# GPduino-T.net
KiCad netlist of a schematic drawn in EAGLE
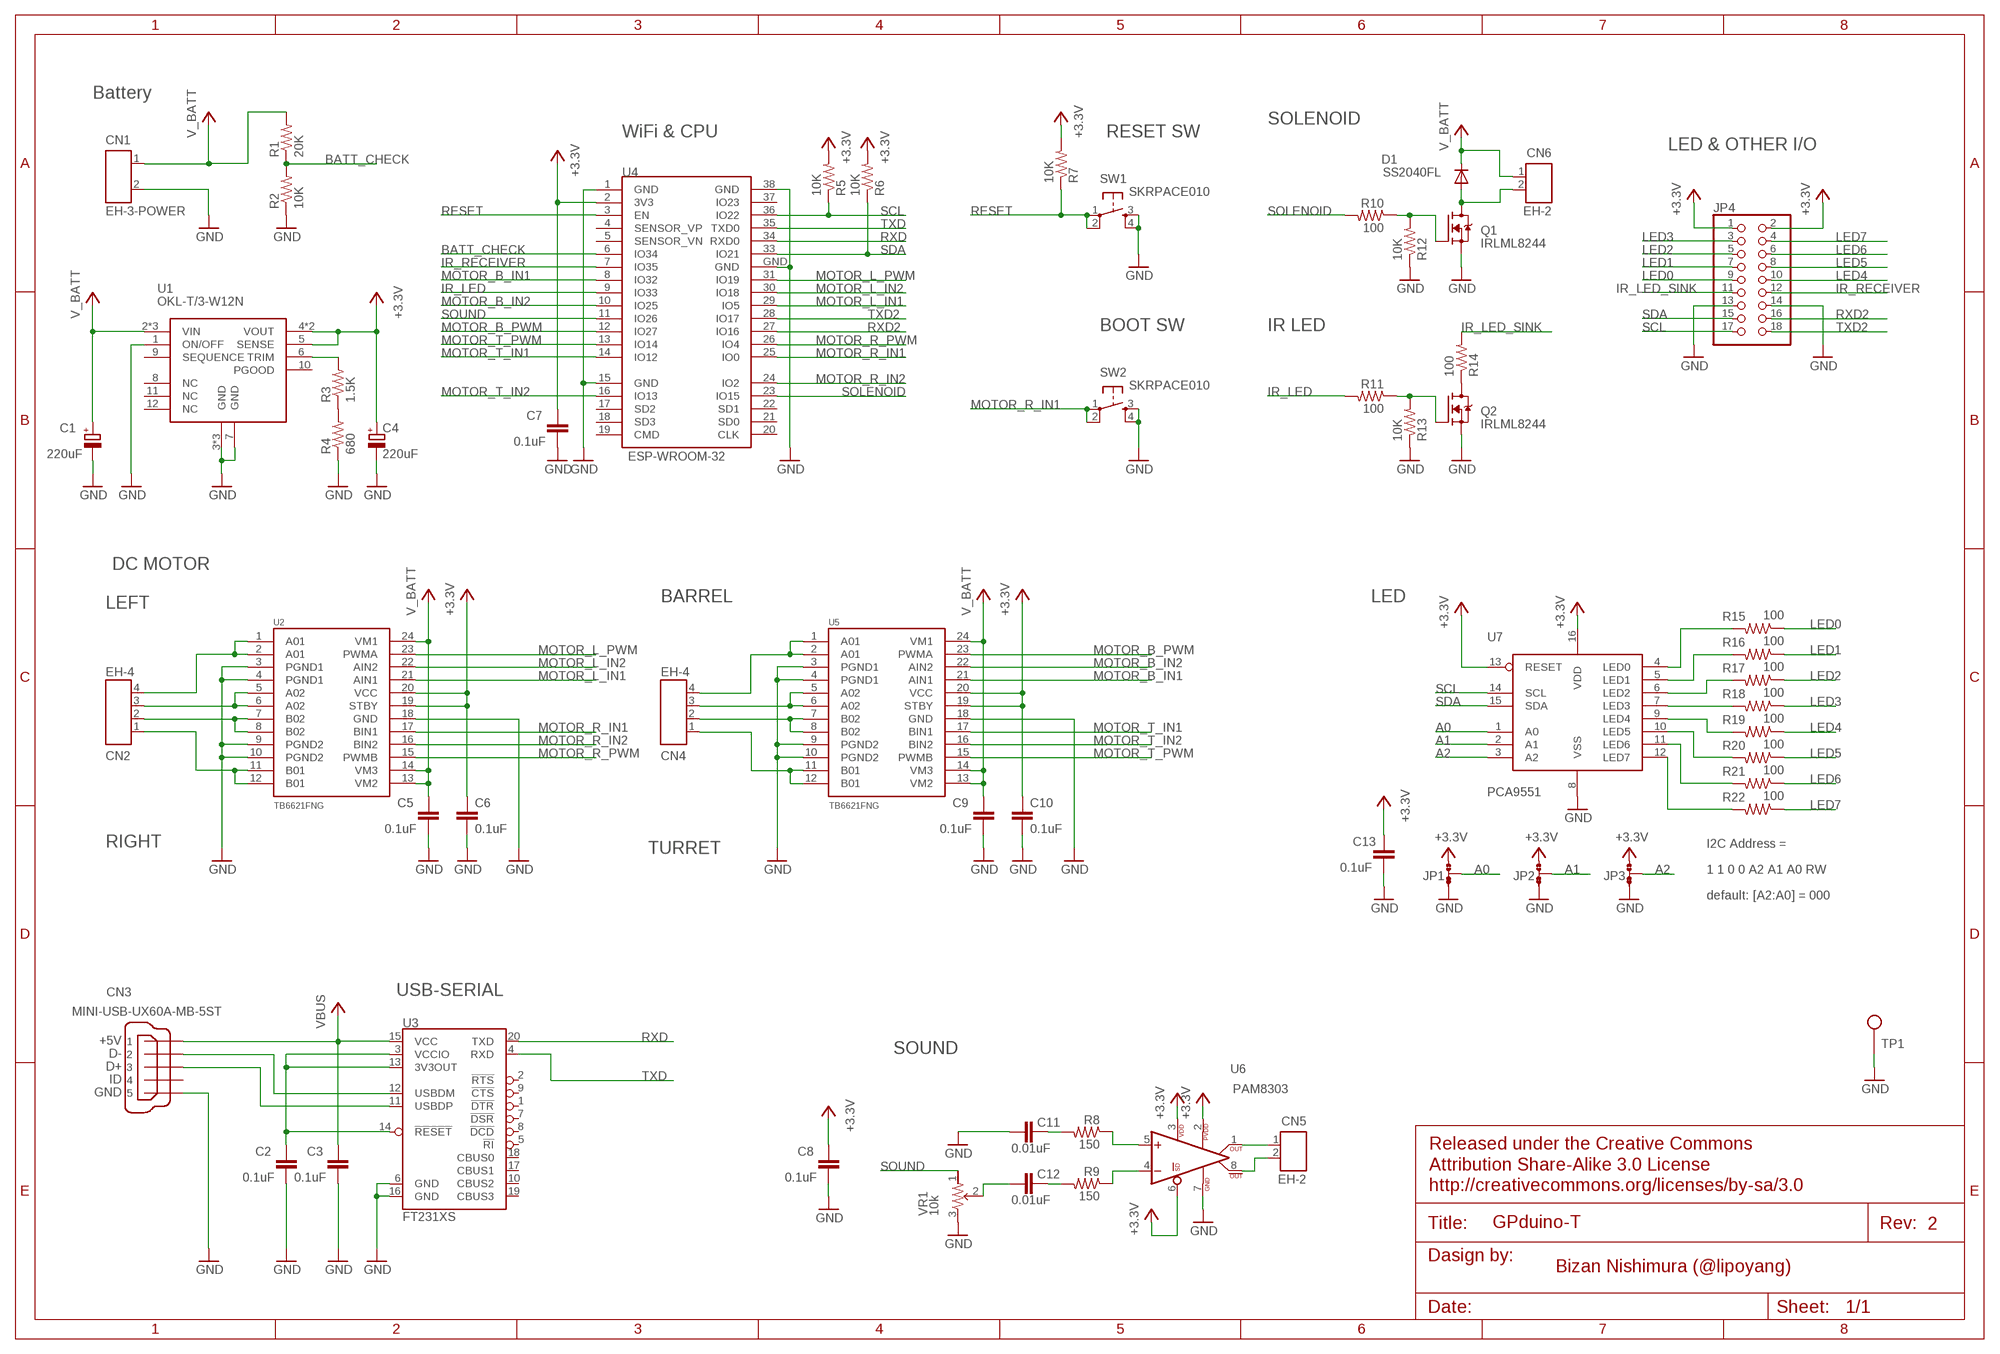
[diagram p0: schematic, sheet 1]

(export (version "E")
  (design (tool "Eeschema 10.0.6"))
  (components
    (comp (ref "C1")
      (value "220uF")
      (footprint "eagle-import:UD-6,3X7,7_NICHICON")
      (libsource (lib "eagle-import") (part "CPOL-EUUD-6,3X7,7"))
    )
    (comp (ref "C2")
      (value "0.1uF")
      (footprint "eagle-import:C1608")
      (libsource (lib "eagle-import") (part "C-EUC1608"))
    )
    (comp (ref "C3")
      (value "0.1uF")
      (footprint "eagle-import:C1608")
      (libsource (lib "eagle-import") (part "C-EUC1608"))
    )
    (comp (ref "C4")
      (value "220uF")
      (footprint "eagle-import:UD-6,3X7,7_NICHICON")
      (libsource (lib "eagle-import") (part "CPOL-EUUD-6,3X7,7"))
    )
    (comp (ref "C5")
      (value "0.1uF")
      (footprint "eagle-import:C1608")
      (libsource (lib "eagle-import") (part "C-EUC1608"))
    )
    (comp (ref "C6")
      (value "0.1uF")
      (footprint "eagle-import:C1608")
      (libsource (lib "eagle-import") (part "C-EUC1608"))
    )
    (comp (ref "C7")
      (value "0.1uF")
      (footprint "eagle-import:C1608")
      (libsource (lib "eagle-import") (part "C-EUC1608"))
    )
    (comp (ref "C8")
      (value "0.1uF")
      (footprint "eagle-import:C1608")
      (libsource (lib "eagle-import") (part "C-EUC1608"))
    )
    (comp (ref "C9")
      (value "0.1uF")
      (footprint "eagle-import:C1608")
      (libsource (lib "eagle-import") (part "C-EUC1608"))
    )
    (comp (ref "C10")
      (value "0.1uF")
      (footprint "eagle-import:C1608")
      (libsource (lib "eagle-import") (part "C-EUC1608"))
    )
    (comp (ref "C11")
      (value "0.01uF")
      (footprint "eagle-import:C1608")
      (libsource (lib "eagle-import") (part "C-EUC1608"))
    )
    (comp (ref "C12")
      (value "0.01uF")
      (footprint "eagle-import:C1608")
      (libsource (lib "eagle-import") (part "C-EUC1608"))
    )
    (comp (ref "C13")
      (value "0.1uF")
      (footprint "eagle-import:C1608")
      (libsource (lib "eagle-import") (part "C-EUC1608"))
    )
    (comp (ref "CN1")
      (value "EH-3-POWER")
      (footprint "eagle-import:EH-3-POWER")
      (libsource (lib "eagle-import") (part "EH-3-POWER"))
    )
    (comp (ref "CN2")
      (value "EH-4")
      (footprint "eagle-import:EH-4")
      (libsource (lib "eagle-import") (part "EH-4"))
    )
    (comp (ref "CN3")
      (value "MINI-USB-UX60A-MB-5ST")
      (footprint "eagle-import:UX60A-MB-5ST")
      (libsource (lib "eagle-import") (part "MINI-USB-UX60A-MB-5ST"))
    )
    (comp (ref "CN4")
      (value "EH-4")
      (footprint "eagle-import:EH-4")
      (libsource (lib "eagle-import") (part "EH-4"))
    )
    (comp (ref "CN5")
      (value "EH-2")
      (footprint "eagle-import:EH-2")
      (libsource (lib "eagle-import") (part "EH-2"))
    )
    (comp (ref "CN6")
      (value "EH-2")
      (footprint "eagle-import:EH-2")
      (libsource (lib "eagle-import") (part "EH-2"))
    )
    (comp (ref "D1")
      (value "SS2040FL")
      (footprint "eagle-import:SOD123")
      (libsource (lib "eagle-import") (part "DIODE-SOD123"))
    )
    (comp (ref "JP1")
      (value "JUMP-SHORTB")
      (footprint "eagle-import:JUMP-SHORT")
      (libsource (lib "eagle-import") (part "JUMP-SHORTB"))
    )
    (comp (ref "JP2")
      (value "JUMP-SHORTB")
      (footprint "eagle-import:JUMP-SHORT")
      (libsource (lib "eagle-import") (part "JUMP-SHORTB"))
    )
    (comp (ref "JP3")
      (value "JUMP-SHORTB")
      (footprint "eagle-import:JUMP-SHORT")
      (libsource (lib "eagle-import") (part "JUMP-SHORTB"))
    )
    (comp (ref "JP4")
      (value "PINHD-2X9")
      (footprint "eagle-import:2X09")
      (libsource (lib "eagle-import") (part "PINHD-2X9"))
    )
    (comp (ref "Q1")
      (value "IRLML8244")
      (footprint "eagle-import:SOT23")
      (libsource (lib "eagle-import") (part "IRLML8244"))
    )
    (comp (ref "Q2")
      (value "IRLML8244")
      (footprint "eagle-import:SOT23")
      (libsource (lib "eagle-import") (part "IRLML8244"))
    )
    (comp (ref "R1")
      (value "20K")
      (footprint "eagle-import:0603-RES")
      (libsource (lib "eagle-import") (part "RESISTOR0603-RES"))
    )
    (comp (ref "R2")
      (value "10K")
      (footprint "eagle-import:0603-RES")
      (libsource (lib "eagle-import") (part "RESISTOR0603-RES"))
    )
    (comp (ref "R3")
      (value "1.5K")
      (footprint "eagle-import:0603-RES")
      (libsource (lib "eagle-import") (part "RESISTOR0603-RES"))
    )
    (comp (ref "R4")
      (value "680")
      (footprint "eagle-import:0603-RES")
      (libsource (lib "eagle-import") (part "RESISTOR0603-RES"))
    )
    (comp (ref "R5")
      (value "10K")
      (footprint "eagle-import:0603-RES")
      (libsource (lib "eagle-import") (part "RESISTOR0603-RES"))
    )
    (comp (ref "R6")
      (value "10K")
      (footprint "eagle-import:0603-RES")
      (libsource (lib "eagle-import") (part "RESISTOR0603-RES"))
    )
    (comp (ref "R7")
      (value "10K")
      (footprint "eagle-import:0603-RES")
      (libsource (lib "eagle-import") (part "RESISTOR0603-RES"))
    )
    (comp (ref "R8")
      (value "150")
      (footprint "eagle-import:0603-RES")
      (libsource (lib "eagle-import") (part "RESISTOR0603-RES"))
    )
    (comp (ref "R9")
      (value "150")
      (footprint "eagle-import:0603-RES")
      (libsource (lib "eagle-import") (part "RESISTOR0603-RES"))
    )
    (comp (ref "R10")
      (value "100")
      (footprint "eagle-import:0603-RES")
      (libsource (lib "eagle-import") (part "RESISTOR0603-RES"))
    )
    (comp (ref "R11")
      (value "100")
      (footprint "eagle-import:0603-RES")
      (libsource (lib "eagle-import") (part "RESISTOR0603-RES"))
    )
    (comp (ref "R12")
      (value "10K")
      (footprint "eagle-import:0603-RES")
      (libsource (lib "eagle-import") (part "RESISTOR0603-RES"))
    )
    (comp (ref "R13")
      (value "10K")
      (footprint "eagle-import:0603-RES")
      (libsource (lib "eagle-import") (part "RESISTOR0603-RES"))
    )
    (comp (ref "R14")
      (value "100")
      (footprint "eagle-import:0603-RES")
      (libsource (lib "eagle-import") (part "RESISTOR0603-RES"))
    )
    (comp (ref "R15")
      (value "100")
      (footprint "eagle-import:0603-RES")
      (libsource (lib "eagle-import") (part "RESISTOR0603-RES"))
    )
    (comp (ref "R16")
      (value "100")
      (footprint "eagle-import:0603-RES")
      (libsource (lib "eagle-import") (part "RESISTOR0603-RES"))
    )
    (comp (ref "R17")
      (value "100")
      (footprint "eagle-import:0603-RES")
      (libsource (lib "eagle-import") (part "RESISTOR0603-RES"))
    )
    (comp (ref "R18")
      (value "100")
      (footprint "eagle-import:0603-RES")
      (libsource (lib "eagle-import") (part "RESISTOR0603-RES"))
    )
    (comp (ref "R19")
      (value "100")
      (footprint "eagle-import:0603-RES")
      (libsource (lib "eagle-import") (part "RESISTOR0603-RES"))
    )
    (comp (ref "R20")
      (value "100")
      (footprint "eagle-import:0603-RES")
      (libsource (lib "eagle-import") (part "RESISTOR0603-RES"))
    )
    (comp (ref "R21")
      (value "100")
      (footprint "eagle-import:0603-RES")
      (libsource (lib "eagle-import") (part "RESISTOR0603-RES"))
    )
    (comp (ref "R22")
      (value "100")
      (footprint "eagle-import:0603-RES")
      (libsource (lib "eagle-import") (part "RESISTOR0603-RES"))
    )
    (comp (ref "SW1")
      (value "SKRPACE010")
      (footprint "eagle-import:SKRPACE010")
      (libsource (lib "eagle-import") (part "SKRPACE010"))
    )
    (comp (ref "SW2")
      (value "SKRPACE010")
      (footprint "eagle-import:SKRPACE010")
      (libsource (lib "eagle-import") (part "SKRPACE010"))
    )
    (comp (ref "TP1")
      (value "TEST_PIN")
      (footprint "eagle-import:TEST_PIN")
      (libsource (lib "eagle-import") (part "TEST_PIN"))
    )
    (comp (ref "U1")
      (value "OKL-T/3-W12N")
      (footprint "eagle-import:OKL-T_X-WXXN")
      (libsource (lib "eagle-import") (part "OKL-T/6-W12N"))
    )
    (comp (ref "U2")
      (value "TB6621FNG")
      (footprint "eagle-import:SSOP24")
      (libsource (lib "eagle-import") (part "TB6621FNG"))
    )
    (comp (ref "U3")
      (value "FT231XS")
      (footprint "eagle-import:SSOP20")
      (libsource (lib "eagle-import") (part "FT231XS"))
    )
    (comp (ref "U4")
      (value "ESP-WROOM-32")
      (footprint "eagle-import:ESP-WROOM-32")
      (libsource (lib "eagle-import") (part "ESP-WROOM-32"))
    )
    (comp (ref "U5")
      (value "TB6621FNG")
      (footprint "eagle-import:SSOP24")
      (libsource (lib "eagle-import") (part "TB6621FNG"))
    )
    (comp (ref "U6")
      (value "PAM8303")
      (footprint "eagle-import:MSOP8")
      (libsource (lib "eagle-import") (part "PAM8303"))
    )
    (comp (ref "U7")
      (value "PCA9551")
      (footprint "eagle-import:TSSOP16")
      (libsource (lib "eagle-import") (part "PCA9551"))
    )
    (comp (ref "VR1")
      (value "10k")
      (footprint "eagle-import:EVM3Y")
      (libsource (lib "eagle-import") (part "R-TRIMM"))
    )
  )
  (nets
    (net (code "1") (name "+3.3V") (class "Default")
      (node (ref "C10") (pin "1") (pinfunction "1_1") (pintype "passive"))
      (node (ref "C13") (pin "1") (pinfunction "1_1") (pintype "passive"))
      (node (ref "C4") (pin "+") (pinfunction "+_+") (pintype "passive"))
      (node (ref "C6") (pin "1") (pinfunction "1_1") (pintype "passive"))
      (node (ref "C7") (pin "1") (pinfunction "1_1") (pintype "passive"))
      (node (ref "C8") (pin "1") (pinfunction "1_1") (pintype "passive"))
      (node (ref "JP1") (pin "1") (pinfunction "1_1") (pintype "passive"))
      (node (ref "JP2") (pin "1") (pinfunction "1_1") (pintype "passive"))
      (node (ref "JP3") (pin "1") (pinfunction "1_1") (pintype "passive"))
      (node (ref "JP4") (pin "1") (pinfunction "1_1") (pintype "passive"))
      (node (ref "JP4") (pin "2") (pinfunction "2_2") (pintype "passive"))
      (node (ref "R5") (pin "2") (pinfunction "2_2") (pintype "passive"))
      (node (ref "R6") (pin "2") (pinfunction "2_2") (pintype "passive"))
      (node (ref "R7") (pin "2") (pinfunction "2_2") (pintype "passive"))
      (node (ref "U1") (pin "4") (pinfunction "VOUT_4") (pintype "power_in"))
      (node (ref "U1") (pin "4@1") (pinfunction "VOUT_4@1") (pintype "power_in"))
      (node (ref "U1") (pin "5") (pinfunction "SENSE_5") (pintype "input"))
      (node (ref "U2") (pin "19") (pinfunction "STBY_19") (pintype "bidirectional"))
      (node (ref "U2") (pin "20") (pinfunction "VCC_20") (pintype "bidirectional"))
      (node (ref "U4") (pin "2") (pinfunction "3V3_2") (pintype "power_in"))
      (node (ref "U5") (pin "19") (pinfunction "STBY_19") (pintype "bidirectional"))
      (node (ref "U5") (pin "20") (pinfunction "VCC_20") (pintype "bidirectional"))
      (node (ref "U6") (pin "2") (pinfunction "PVDD_2") (pintype "power_in"))
      (node (ref "U6") (pin "3") (pinfunction "VDD_3") (pintype "power_in"))
      (node (ref "U6") (pin "6") (pinfunction "SD_6") (pintype "input"))
      (node (ref "U7") (pin "13") (pinfunction "RESET_13") (pintype "input"))
      (node (ref "U7") (pin "16") (pinfunction "VDD_16") (pintype "power_in"))
    )
    (net (code "2") (name "/A0") (class "Default")
      (node (ref "JP1") (pin "2") (pinfunction "2_2") (pintype "passive"))
      (node (ref "U7") (pin "1") (pinfunction "A0_1") (pintype "input"))
    )
    (net (code "3") (name "/A1") (class "Default")
      (node (ref "JP2") (pin "2") (pinfunction "2_2") (pintype "passive"))
      (node (ref "U7") (pin "2") (pinfunction "A1_2") (pintype "input"))
    )
    (net (code "4") (name "/A2") (class "Default")
      (node (ref "JP3") (pin "2") (pinfunction "2_2") (pintype "passive"))
      (node (ref "U7") (pin "3") (pinfunction "A2_3") (pintype "input"))
    )
    (net (code "5") (name "/BATT_CHECK") (class "Default")
      (node (ref "R1") (pin "1") (pinfunction "1_1") (pintype "passive"))
      (node (ref "R2") (pin "2") (pinfunction "2_2") (pintype "passive"))
      (node (ref "U4") (pin "6") (pinfunction "IO34_6") (pintype "bidirectional"))
    )
    (net (code "6") (name "/IR_LED") (class "Default")
      (node (ref "R11") (pin "2") (pinfunction "2_2") (pintype "passive"))
      (node (ref "U4") (pin "9") (pinfunction "IO33_9") (pintype "bidirectional"))
    )
    (net (code "7") (name "/IR_LED_SINK") (class "Default")
      (node (ref "JP4") (pin "11") (pinfunction "11_11") (pintype "passive"))
      (node (ref "R14") (pin "2") (pinfunction "2_2") (pintype "passive"))
    )
    (net (code "8") (name "/IR_RECEIVER") (class "Default")
      (node (ref "JP4") (pin "12") (pinfunction "12_12") (pintype "passive"))
      (node (ref "U4") (pin "7") (pinfunction "IO35_7") (pintype "bidirectional"))
    )
    (net (code "9") (name "/LED0") (class "Default")
      (node (ref "JP4") (pin "9") (pinfunction "9_9") (pintype "passive"))
      (node (ref "R15") (pin "1") (pinfunction "1_1") (pintype "passive"))
    )
    (net (code "10") (name "/LED1") (class "Default")
      (node (ref "JP4") (pin "7") (pinfunction "7_7") (pintype "passive"))
      (node (ref "R16") (pin "1") (pinfunction "1_1") (pintype "passive"))
    )
    (net (code "11") (name "/LED2") (class "Default")
      (node (ref "JP4") (pin "5") (pinfunction "5_5") (pintype "passive"))
      (node (ref "R17") (pin "1") (pinfunction "1_1") (pintype "passive"))
    )
    (net (code "12") (name "/LED3") (class "Default")
      (node (ref "JP4") (pin "3") (pinfunction "3_3") (pintype "passive"))
      (node (ref "R18") (pin "1") (pinfunction "1_1") (pintype "passive"))
    )
    (net (code "13") (name "/LED4") (class "Default")
      (node (ref "JP4") (pin "10") (pinfunction "10_10") (pintype "passive"))
      (node (ref "R19") (pin "1") (pinfunction "1_1") (pintype "passive"))
    )
    (net (code "14") (name "/LED5") (class "Default")
      (node (ref "JP4") (pin "8") (pinfunction "8_8") (pintype "passive"))
      (node (ref "R20") (pin "1") (pinfunction "1_1") (pintype "passive"))
    )
    (net (code "15") (name "/LED6") (class "Default")
      (node (ref "JP4") (pin "6") (pinfunction "6_6") (pintype "passive"))
      (node (ref "R21") (pin "1") (pinfunction "1_1") (pintype "passive"))
    )
    (net (code "16") (name "/LED7") (class "Default")
      (node (ref "JP4") (pin "4") (pinfunction "4_4") (pintype "passive"))
      (node (ref "R22") (pin "1") (pinfunction "1_1") (pintype "passive"))
    )
    (net (code "17") (name "/MOTOR_B_IN1") (class "Default")
      (node (ref "U4") (pin "8") (pinfunction "IO32_8") (pintype "bidirectional"))
      (node (ref "U5") (pin "21") (pinfunction "AIN1_21") (pintype "bidirectional"))
    )
    (net (code "18") (name "/MOTOR_B_IN2") (class "Default")
      (node (ref "U4") (pin "10") (pinfunction "IO25_10") (pintype "bidirectional"))
      (node (ref "U5") (pin "22") (pinfunction "AIN2_22") (pintype "bidirectional"))
    )
    (net (code "19") (name "/MOTOR_B_PWM") (class "Default")
      (node (ref "U4") (pin "12") (pinfunction "IO27_12") (pintype "bidirectional"))
      (node (ref "U5") (pin "23") (pinfunction "PWMA_23") (pintype "bidirectional"))
    )
    (net (code "20") (name "/MOTOR_L_IN1") (class "Default")
      (node (ref "U2") (pin "21") (pinfunction "AIN1_21") (pintype "bidirectional"))
      (node (ref "U4") (pin "29") (pinfunction "IO5_29") (pintype "bidirectional"))
    )
    (net (code "21") (name "/MOTOR_L_IN2") (class "Default")
      (node (ref "U2") (pin "22") (pinfunction "AIN2_22") (pintype "bidirectional"))
      (node (ref "U4") (pin "30") (pinfunction "IO18_30") (pintype "bidirectional"))
    )
    (net (code "22") (name "/MOTOR_L_PWM") (class "Default")
      (node (ref "U2") (pin "23") (pinfunction "PWMA_23") (pintype "bidirectional"))
      (node (ref "U4") (pin "31") (pinfunction "IO19_31") (pintype "bidirectional"))
    )
    (net (code "23") (name "/MOTOR_R_IN1") (class "Default")
      (node (ref "SW2") (pin "1") (pinfunction "1_1") (pintype "passive"))
      (node (ref "SW2") (pin "2") (pinfunction "2_2") (pintype "passive"))
      (node (ref "U2") (pin "17") (pinfunction "BIN1_17") (pintype "bidirectional"))
      (node (ref "U4") (pin "25") (pinfunction "IO0_25") (pintype "bidirectional"))
    )
    (net (code "24") (name "/MOTOR_R_IN2") (class "Default")
      (node (ref "U2") (pin "16") (pinfunction "BIN2_16") (pintype "bidirectional"))
      (node (ref "U4") (pin "24") (pinfunction "IO2_24") (pintype "bidirectional"))
    )
    (net (code "25") (name "/MOTOR_R_PWM") (class "Default")
      (node (ref "U2") (pin "15") (pinfunction "PWMB_15") (pintype "bidirectional"))
      (node (ref "U4") (pin "26") (pinfunction "IO4_26") (pintype "bidirectional"))
    )
    (net (code "26") (name "/MOTOR_T_IN1") (class "Default")
      (node (ref "U4") (pin "14") (pinfunction "IO12_14") (pintype "bidirectional"))
      (node (ref "U5") (pin "17") (pinfunction "BIN1_17") (pintype "bidirectional"))
    )
    (net (code "27") (name "/MOTOR_T_IN2") (class "Default")
      (node (ref "U4") (pin "16") (pinfunction "IO13_16") (pintype "bidirectional"))
      (node (ref "U5") (pin "16") (pinfunction "BIN2_16") (pintype "bidirectional"))
    )
    (net (code "28") (name "/MOTOR_T_PWM") (class "Default")
      (node (ref "U4") (pin "13") (pinfunction "IO14_13") (pintype "bidirectional"))
      (node (ref "U5") (pin "15") (pinfunction "PWMB_15") (pintype "bidirectional"))
    )
    (net (code "29") (name "/RESET") (class "Default")
      (node (ref "R7") (pin "1") (pinfunction "1_1") (pintype "passive"))
      (node (ref "SW1") (pin "1") (pinfunction "1_1") (pintype "passive"))
      (node (ref "SW1") (pin "2") (pinfunction "2_2") (pintype "passive"))
      (node (ref "U4") (pin "3") (pinfunction "EN_3") (pintype "input"))
    )
    (net (code "30") (name "/RXD") (class "Default")
      (node (ref "U3") (pin "20") (pinfunction "TXD_20") (pintype "bidirectional"))
      (node (ref "U4") (pin "34") (pinfunction "RXD0_34") (pintype "bidirectional"))
    )
    (net (code "31") (name "/RXD2") (class "Default")
      (node (ref "JP4") (pin "16") (pinfunction "16_16") (pintype "passive"))
      (node (ref "U4") (pin "27") (pinfunction "IO16_27") (pintype "bidirectional"))
    )
    (net (code "32") (name "/SCL") (class "Default")
      (node (ref "JP4") (pin "17") (pinfunction "17_17") (pintype "passive"))
      (node (ref "R5") (pin "1") (pinfunction "1_1") (pintype "passive"))
      (node (ref "U4") (pin "36") (pinfunction "IO22_36") (pintype "bidirectional"))
      (node (ref "U7") (pin "14") (pinfunction "SCL_14") (pintype "bidirectional"))
    )
    (net (code "33") (name "/SDA") (class "Default")
      (node (ref "JP4") (pin "15") (pinfunction "15_15") (pintype "passive"))
      (node (ref "R6") (pin "1") (pinfunction "1_1") (pintype "passive"))
      (node (ref "U4") (pin "33") (pinfunction "IO21_33") (pintype "bidirectional"))
      (node (ref "U7") (pin "15") (pinfunction "SDA_15") (pintype "bidirectional"))
    )
    (net (code "34") (name "/SOLENOID") (class "Default")
      (node (ref "R10") (pin "2") (pinfunction "2_2") (pintype "passive"))
      (node (ref "U4") (pin "23") (pinfunction "IO15_23") (pintype "bidirectional"))
    )
    (net (code "35") (name "/SOUND") (class "Default")
      (node (ref "U4") (pin "11") (pinfunction "IO26_11") (pintype "bidirectional"))
      (node (ref "VR1") (pin "1") (pinfunction "E_1") (pintype "passive"))
    )
    (net (code "36") (name "/TXD") (class "Default")
      (node (ref "U3") (pin "4") (pinfunction "RXD_4") (pintype "bidirectional"))
      (node (ref "U4") (pin "35") (pinfunction "TXD0_35") (pintype "bidirectional"))
    )
    (net (code "37") (name "/TXD2") (class "Default")
      (node (ref "JP4") (pin "18") (pinfunction "18_18") (pintype "passive"))
      (node (ref "U4") (pin "28") (pinfunction "IO17_28") (pintype "bidirectional"))
    )
    (net (code "38") (name "GND") (class "Default")
      (node (ref "C1") (pin "-") (pinfunction "-_-") (pintype "passive"))
      (node (ref "C10") (pin "2") (pinfunction "2_2") (pintype "passive"))
      (node (ref "C11") (pin "2") (pinfunction "2_2") (pintype "passive"))
      (node (ref "C13") (pin "2") (pinfunction "2_2") (pintype "passive"))
      (node (ref "C2") (pin "2") (pinfunction "2_2") (pintype "passive"))
      (node (ref "C3") (pin "2") (pinfunction "2_2") (pintype "passive"))
      (node (ref "C4") (pin "-") (pinfunction "-_-") (pintype "passive"))
      (node (ref "C5") (pin "2") (pinfunction "2_2") (pintype "passive"))
      (node (ref "C6") (pin "2") (pinfunction "2_2") (pintype "passive"))
      (node (ref "C7") (pin "2") (pinfunction "2_2") (pintype "passive"))
      (node (ref "C8") (pin "2") (pinfunction "2_2") (pintype "passive"))
      (node (ref "C9") (pin "2") (pinfunction "2_2") (pintype "passive"))
      (node (ref "CN1") (pin "2") (pinfunction "2_2") (pintype "bidirectional"))
      (node (ref "CN3") (pin "5") (pinfunction "5_5") (pintype "input"))
      (node (ref "JP1") (pin "3") (pinfunction "3_3") (pintype "passive"))
      (node (ref "JP2") (pin "3") (pinfunction "3_3") (pintype "passive"))
      (node (ref "JP3") (pin "3") (pinfunction "3_3") (pintype "passive"))
      (node (ref "JP4") (pin "13") (pinfunction "13_13") (pintype "passive"))
      (node (ref "JP4") (pin "14") (pinfunction "14_14") (pintype "passive"))
      (node (ref "Q1") (pin "2") (pinfunction "S_2") (pintype "passive"))
      (node (ref "Q2") (pin "2") (pinfunction "S_2") (pintype "passive"))
      (node (ref "R12") (pin "1") (pinfunction "1_1") (pintype "passive"))
      (node (ref "R13") (pin "1") (pinfunction "1_1") (pintype "passive"))
      (node (ref "R2") (pin "1") (pinfunction "1_1") (pintype "passive"))
      (node (ref "R4") (pin "1") (pinfunction "1_1") (pintype "passive"))
      (node (ref "SW1") (pin "3") (pinfunction "3_3") (pintype "passive"))
      (node (ref "SW1") (pin "4") (pinfunction "4_4") (pintype "passive"))
      (node (ref "SW2") (pin "3") (pinfunction "3_3") (pintype "passive"))
      (node (ref "SW2") (pin "4") (pinfunction "4_4") (pintype "passive"))
      (node (ref "TP1") (pin "1") (pinfunction "P$1_1") (pintype "bidirectional"))
      (node (ref "U1") (pin "1") (pinfunction "ON/OFF_1") (pintype "input"))
      (node (ref "U1") (pin "3") (pinfunction "GND_3") (pintype "power_in"))
      (node (ref "U1") (pin "3@2") (pinfunction "GND_3@2") (pintype "power_in"))
      (node (ref "U1") (pin "3@3") (pinfunction "GND_3@3") (pintype "power_in"))
      (node (ref "U1") (pin "7") (pinfunction "GND_7") (pintype "power_in"))
      (node (ref "U2") (pin "10") (pinfunction "PGND2_10") (pintype "bidirectional"))
      (node (ref "U2") (pin "18") (pinfunction "GND_18") (pintype "bidirectional"))
      (node (ref "U2") (pin "3") (pinfunction "PGND1_3") (pintype "bidirectional"))
      (node (ref "U2") (pin "4") (pinfunction "PGND1_4") (pintype "bidirectional"))
      (node (ref "U2") (pin "9") (pinfunction "PGND2_9") (pintype "bidirectional"))
      (node (ref "U3") (pin "16") (pinfunction "GND_16") (pintype "bidirectional"))
      (node (ref "U3") (pin "6") (pinfunction "GND_6") (pintype "bidirectional"))
      (node (ref "U4") (pin "1") (pinfunction "GND_1") (pintype "power_in"))
      (node (ref "U4") (pin "15") (pinfunction "GND_15") (pintype "power_in"))
      (node (ref "U4") (pin "38") (pinfunction "GND_38") (pintype "power_in"))
      (node (ref "U4") (pin "GND") (pinfunction "GND_GND") (pintype "power_in"))
      (node (ref "U5") (pin "10") (pinfunction "PGND2_10") (pintype "bidirectional"))
      (node (ref "U5") (pin "18") (pinfunction "GND_18") (pintype "bidirectional"))
      (node (ref "U5") (pin "3") (pinfunction "PGND1_3") (pintype "bidirectional"))
      (node (ref "U5") (pin "4") (pinfunction "PGND1_4") (pintype "bidirectional"))
      (node (ref "U5") (pin "9") (pinfunction "PGND2_9") (pintype "bidirectional"))
      (node (ref "U6") (pin "7") (pinfunction "GND_7") (pintype "power_in"))
      (node (ref "U7") (pin "8") (pinfunction "VSS_8") (pintype "power_in"))
      (node (ref "VR1") (pin "3") (pinfunction "A_3") (pintype "passive"))
    )
    (net (code "39") (name "Net-(C11-Pad1)") (class "Default")
      (node (ref "C11") (pin "1") (pinfunction "1_1") (pintype "passive"))
      (node (ref "R8") (pin "2") (pinfunction "2_2") (pintype "passive"))
    )
    (net (code "40") (name "Net-(C12-Pad1)") (class "Default")
      (node (ref "C12") (pin "1") (pinfunction "1_1") (pintype "passive"))
      (node (ref "R9") (pin "2") (pinfunction "2_2") (pintype "passive"))
    )
    (net (code "41") (name "Net-(CN2-Pad1)") (class "Default")
      (node (ref "CN2") (pin "1") (pinfunction "1_1") (pintype "bidirectional"))
      (node (ref "U2") (pin "11") (pinfunction "B01_11") (pintype "bidirectional"))
      (node (ref "U2") (pin "12") (pinfunction "B01_12") (pintype "bidirectional"))
    )
    (net (code "42") (name "Net-(CN2-Pad2)") (class "Default")
      (node (ref "CN2") (pin "2") (pinfunction "2_2") (pintype "bidirectional"))
      (node (ref "U2") (pin "7") (pinfunction "B02_7") (pintype "bidirectional"))
      (node (ref "U2") (pin "8") (pinfunction "B02_8") (pintype "bidirectional"))
    )
    (net (code "43") (name "Net-(CN2-Pad3)") (class "Default")
      (node (ref "CN2") (pin "3") (pinfunction "3_3") (pintype "bidirectional"))
      (node (ref "U2") (pin "5") (pinfunction "A02_5") (pintype "bidirectional"))
      (node (ref "U2") (pin "6") (pinfunction "A02_6") (pintype "bidirectional"))
    )
    (net (code "44") (name "Net-(CN2-Pad4)") (class "Default")
      (node (ref "CN2") (pin "4") (pinfunction "4_4") (pintype "bidirectional"))
      (node (ref "U2") (pin "1") (pinfunction "A01_1") (pintype "bidirectional"))
      (node (ref "U2") (pin "2") (pinfunction "A01_2") (pintype "bidirectional"))
    )
    (net (code "45") (name "Net-(CN4-Pad1)") (class "Default")
      (node (ref "CN4") (pin "1") (pinfunction "1_1") (pintype "bidirectional"))
      (node (ref "U5") (pin "11") (pinfunction "B01_11") (pintype "bidirectional"))
      (node (ref "U5") (pin "12") (pinfunction "B01_12") (pintype "bidirectional"))
    )
    (net (code "46") (name "Net-(CN4-Pad2)") (class "Default")
      (node (ref "CN4") (pin "2") (pinfunction "2_2") (pintype "bidirectional"))
      (node (ref "U5") (pin "7") (pinfunction "B02_7") (pintype "bidirectional"))
      (node (ref "U5") (pin "8") (pinfunction "B02_8") (pintype "bidirectional"))
    )
    (net (code "47") (name "Net-(CN4-Pad3)") (class "Default")
      (node (ref "CN4") (pin "3") (pinfunction "3_3") (pintype "bidirectional"))
      (node (ref "U5") (pin "5") (pinfunction "A02_5") (pintype "bidirectional"))
      (node (ref "U5") (pin "6") (pinfunction "A02_6") (pintype "bidirectional"))
    )
    (net (code "48") (name "Net-(CN4-Pad4)") (class "Default")
      (node (ref "CN4") (pin "4") (pinfunction "4_4") (pintype "bidirectional"))
      (node (ref "U5") (pin "1") (pinfunction "A01_1") (pintype "bidirectional"))
      (node (ref "U5") (pin "2") (pinfunction "A01_2") (pintype "bidirectional"))
    )
    (net (code "49") (name "Net-(Q1-D)") (class "Default")
      (node (ref "CN6") (pin "2") (pinfunction "2_2") (pintype "bidirectional"))
      (node (ref "D1") (pin "A") (pinfunction "A_A") (pintype "passive"))
      (node (ref "Q1") (pin "3") (pinfunction "D_3") (pintype "passive"))
    )
    (net (code "50") (name "Net-(Q1-G)") (class "Default")
      (node (ref "Q1") (pin "1") (pinfunction "G_1") (pintype "passive"))
      (node (ref "R10") (pin "1") (pinfunction "1_1") (pintype "passive"))
      (node (ref "R12") (pin "2") (pinfunction "2_2") (pintype "passive"))
    )
    (net (code "51") (name "Net-(Q2-D)") (class "Default")
      (node (ref "Q2") (pin "3") (pinfunction "D_3") (pintype "passive"))
      (node (ref "R14") (pin "1") (pinfunction "1_1") (pintype "passive"))
    )
    (net (code "52") (name "Net-(Q2-G)") (class "Default")
      (node (ref "Q2") (pin "1") (pinfunction "G_1") (pintype "passive"))
      (node (ref "R11") (pin "1") (pinfunction "1_1") (pintype "passive"))
      (node (ref "R13") (pin "2") (pinfunction "2_2") (pintype "passive"))
    )
    (net (code "53") (name "Net-(R3-Pad1)") (class "Default")
      (node (ref "R3") (pin "1") (pinfunction "1_1") (pintype "passive"))
      (node (ref "R4") (pin "2") (pinfunction "2_2") (pintype "passive"))
    )
    (net (code "54") (name "Net-(U1-TRIM)") (class "Default")
      (node (ref "R3") (pin "2") (pinfunction "2_2") (pintype "passive"))
      (node (ref "U1") (pin "6") (pinfunction "TRIM_6") (pintype "input"))
    )
    (net (code "55") (name "Net-(U3-3V3OUT)") (class "Default")
      (node (ref "C2") (pin "1") (pinfunction "1_1") (pintype "passive"))
      (node (ref "U3") (pin "13") (pinfunction "3V3OUT_13") (pintype "bidirectional"))
      (node (ref "U3") (pin "14") (pinfunction "~{RESET}_14") (pintype "bidirectional"))
      (node (ref "U3") (pin "3") (pinfunction "VCCIO_3") (pintype "bidirectional"))
    )
    (net (code "56") (name "Net-(U3-USBDM)") (class "Default")
      (node (ref "CN3") (pin "2") (pinfunction "2_2") (pintype "input"))
      (node (ref "U3") (pin "12") (pinfunction "USBDM_12") (pintype "bidirectional"))
    )
    (net (code "57") (name "Net-(U3-USBDP)") (class "Default")
      (node (ref "CN3") (pin "3") (pinfunction "3_3") (pintype "input"))
      (node (ref "U3") (pin "11") (pinfunction "USBDP_11") (pintype "bidirectional"))
    )
    (net (code "58") (name "Net-(U6-IN+)") (class "Default")
      (node (ref "R8") (pin "1") (pinfunction "1_1") (pintype "passive"))
      (node (ref "U6") (pin "5") (pinfunction "IN+_5") (pintype "input"))
    )
    (net (code "59") (name "Net-(U6-IN-)") (class "Default")
      (node (ref "R9") (pin "1") (pinfunction "1_1") (pintype "passive"))
      (node (ref "U6") (pin "4") (pinfunction "IN-_4") (pintype "input"))
    )
    (net (code "60") (name "Net-(U6-OUT+)") (class "Default")
      (node (ref "CN5") (pin "1") (pinfunction "1_1") (pintype "bidirectional"))
      (node (ref "U6") (pin "1") (pinfunction "OUT+_1") (pintype "output"))
    )
    (net (code "61") (name "Net-(U6-OUT-)") (class "Default")
      (node (ref "CN5") (pin "2") (pinfunction "2_2") (pintype "bidirectional"))
      (node (ref "U6") (pin "8") (pinfunction "OUT-_8") (pintype "output"))
    )
    (net (code "62") (name "Net-(U7-LED0)") (class "Default")
      (node (ref "R15") (pin "2") (pinfunction "2_2") (pintype "passive"))
      (node (ref "U7") (pin "4") (pinfunction "LED0_4") (pintype "bidirectional"))
    )
    (net (code "63") (name "Net-(U7-LED1)") (class "Default")
      (node (ref "R16") (pin "2") (pinfunction "2_2") (pintype "passive"))
      (node (ref "U7") (pin "5") (pinfunction "LED1_5") (pintype "bidirectional"))
    )
    (net (code "64") (name "Net-(U7-LED2)") (class "Default")
      (node (ref "R17") (pin "2") (pinfunction "2_2") (pintype "passive"))
      (node (ref "U7") (pin "6") (pinfunction "LED2_6") (pintype "bidirectional"))
    )
    (net (code "65") (name "Net-(U7-LED3)") (class "Default")
      (node (ref "R18") (pin "2") (pinfunction "2_2") (pintype "passive"))
      (node (ref "U7") (pin "7") (pinfunction "LED3_7") (pintype "bidirectional"))
    )
    (net (code "66") (name "Net-(U7-LED4)") (class "Default")
      (node (ref "R19") (pin "2") (pinfunction "2_2") (pintype "passive"))
      (node (ref "U7") (pin "9") (pinfunction "LED4_9") (pintype "bidirectional"))
    )
    (net (code "67") (name "Net-(U7-LED5)") (class "Default")
      (node (ref "R20") (pin "2") (pinfunction "2_2") (pintype "passive"))
      (node (ref "U7") (pin "10") (pinfunction "LED5_10") (pintype "bidirectional"))
    )
    (net (code "68") (name "Net-(U7-LED6)") (class "Default")
      (node (ref "R21") (pin "2") (pinfunction "2_2") (pintype "passive"))
      (node (ref "U7") (pin "11") (pinfunction "LED6_11") (pintype "bidirectional"))
    )
    (net (code "69") (name "Net-(U7-LED7)") (class "Default")
      (node (ref "R22") (pin "2") (pinfunction "2_2") (pintype "passive"))
      (node (ref "U7") (pin "12") (pinfunction "LED7_12") (pintype "bidirectional"))
    )
    (net (code "70") (name "Net-(VR1-S)") (class "Default")
      (node (ref "C12") (pin "2") (pinfunction "2_2") (pintype "passive"))
      (node (ref "VR1") (pin "2") (pinfunction "S_2") (pintype "passive"))
    )
    (net (code "71") (name "VBUS") (class "Default")
      (node (ref "C3") (pin "1") (pinfunction "1_1") (pintype "passive"))
      (node (ref "CN3") (pin "1") (pinfunction "1_1") (pintype "input"))
      (node (ref "U3") (pin "15") (pinfunction "VCC_15") (pintype "bidirectional"))
    )
    (net (code "72") (name "V_BATT") (class "Default")
      (node (ref "C1") (pin "+") (pinfunction "+_+") (pintype "passive"))
      (node (ref "C5") (pin "1") (pinfunction "1_1") (pintype "passive"))
      (node (ref "C9") (pin "1") (pinfunction "1_1") (pintype "passive"))
      (node (ref "CN1") (pin "1") (pinfunction "1_1") (pintype "bidirectional"))
      (node (ref "CN6") (pin "1") (pinfunction "1_1") (pintype "bidirectional"))
      (node (ref "D1") (pin "C") (pinfunction "C_C") (pintype "passive"))
      (node (ref "R1") (pin "2") (pinfunction "2_2") (pintype "passive"))
      (node (ref "U1") (pin "2") (pinfunction "VIN_2") (pintype "power_in"))
      (node (ref "U1") (pin "2@2") (pinfunction "VIN_2@2") (pintype "power_in"))
      (node (ref "U1") (pin "2@3") (pinfunction "VIN_2@3") (pintype "power_in"))
      (node (ref "U2") (pin "13") (pinfunction "VM2_13") (pintype "bidirectional"))
      (node (ref "U2") (pin "14") (pinfunction "VM3_14") (pintype "bidirectional"))
      (node (ref "U2") (pin "24") (pinfunction "VM1_24") (pintype "bidirectional"))
      (node (ref "U5") (pin "13") (pinfunction "VM2_13") (pintype "bidirectional"))
      (node (ref "U5") (pin "14") (pinfunction "VM3_14") (pintype "bidirectional"))
      (node (ref "U5") (pin "24") (pinfunction "VM1_24") (pintype "bidirectional"))
    )
    (net (code "73") (name "unconnected-(CN3-Pad4)") (class "Default")
      (node (ref "CN3") (pin "4") (pinfunction "4_4") (pintype "bidirectional"))
    )
    (net (code "74") (name "unconnected-(U1-NC-Pad8)") (class "Default")
      (node (ref "U1") (pin "8") (pinfunction "NC_8") (pintype "no_connect"))
    )
    (net (code "75") (name "unconnected-(U1-NC-Pad11)") (class "Default")
      (node (ref "U1") (pin "11") (pinfunction "NC_11") (pintype "no_connect"))
    )
    (net (code "76") (name "unconnected-(U1-NC-Pad12)") (class "Default")
      (node (ref "U1") (pin "12") (pinfunction "NC_12") (pintype "bidirectional"))
    )
    (net (code "77") (name "unconnected-(U1-PGOOD-Pad10)") (class "Default")
      (node (ref "U1") (pin "10") (pinfunction "PGOOD_10") (pintype "open_collector"))
    )
    (net (code "78") (name "unconnected-(U1-SEQUENCE-Pad9)") (class "Default")
      (node (ref "U1") (pin "9") (pinfunction "SEQUENCE_9") (pintype "input"))
    )
    (net (code "79") (name "unconnected-(U3-CBUS0-Pad18)") (class "Default")
      (node (ref "U3") (pin "18") (pinfunction "CBUS0_18") (pintype "bidirectional"))
    )
    (net (code "80") (name "unconnected-(U3-CBUS1-Pad17)") (class "Default")
      (node (ref "U3") (pin "17") (pinfunction "CBUS1_17") (pintype "bidirectional"))
    )
    (net (code "81") (name "unconnected-(U3-CBUS2-Pad10)") (class "Default")
      (node (ref "U3") (pin "10") (pinfunction "CBUS2_10") (pintype "bidirectional"))
    )
    (net (code "82") (name "unconnected-(U3-CBUS3-Pad19)") (class "Default")
      (node (ref "U3") (pin "19") (pinfunction "CBUS3_19") (pintype "bidirectional"))
    )
    (net (code "83") (name "unconnected-(U3-~{CTS}-Pad9)") (class "Default")
      (node (ref "U3") (pin "9") (pinfunction "~{CTS}_9") (pintype "bidirectional"))
    )
    (net (code "84") (name "unconnected-(U3-~{DCD}-Pad8)") (class "Default")
      (node (ref "U3") (pin "8") (pinfunction "~{DCD}_8") (pintype "bidirectional"))
    )
    (net (code "85") (name "unconnected-(U3-~{DSR}-Pad7)") (class "Default")
      (node (ref "U3") (pin "7") (pinfunction "~{DSR}_7") (pintype "bidirectional"))
    )
    (net (code "86") (name "unconnected-(U3-~{DTR}-Pad1)") (class "Default")
      (node (ref "U3") (pin "1") (pinfunction "~{DTR}_1") (pintype "bidirectional"))
    )
    (net (code "87") (name "unconnected-(U3-~{RI}-Pad5)") (class "Default")
      (node (ref "U3") (pin "5") (pinfunction "~{RI}_5") (pintype "bidirectional"))
    )
    (net (code "88") (name "unconnected-(U3-~{RTS}-Pad2)") (class "Default")
      (node (ref "U3") (pin "2") (pinfunction "~{RTS}_2") (pintype "bidirectional"))
    )
    (net (code "89") (name "unconnected-(U4-CLK-Pad20)") (class "Default")
      (node (ref "U4") (pin "20") (pinfunction "CLK_20") (pintype "bidirectional"))
    )
    (net (code "90") (name "unconnected-(U4-CMD-Pad19)") (class "Default")
      (node (ref "U4") (pin "19") (pinfunction "CMD_19") (pintype "bidirectional"))
    )
    (net (code "91") (name "unconnected-(U4-IO23-Pad37)") (class "Default")
      (node (ref "U4") (pin "37") (pinfunction "IO23_37") (pintype "bidirectional"))
    )
    (net (code "92") (name "unconnected-(U4-SD0-Pad21)") (class "Default")
      (node (ref "U4") (pin "21") (pinfunction "SD0_21") (pintype "bidirectional"))
    )
    (net (code "93") (name "unconnected-(U4-SD1-Pad22)") (class "Default")
      (node (ref "U4") (pin "22") (pinfunction "SD1_22") (pintype "bidirectional"))
    )
    (net (code "94") (name "unconnected-(U4-SD2-Pad17)") (class "Default")
      (node (ref "U4") (pin "17") (pinfunction "SD2_17") (pintype "bidirectional"))
    )
    (net (code "95") (name "unconnected-(U4-SD3-Pad18)") (class "Default")
      (node (ref "U4") (pin "18") (pinfunction "SD3_18") (pintype "bidirectional"))
    )
    (net (code "96") (name "unconnected-(U4-SENSOR_VN-Pad5)") (class "Default")
      (node (ref "U4") (pin "5") (pinfunction "SENSOR_VN_5") (pintype "bidirectional"))
    )
    (net (code "97") (name "unconnected-(U4-SENSOR_VP-Pad4)") (class "Default")
      (node (ref "U4") (pin "4") (pinfunction "SENSOR_VP_4") (pintype "bidirectional"))
    )
  )
)
